# Jacks_EDCPSU.net
KiCad netlist of a schematic drawn in EAGLE
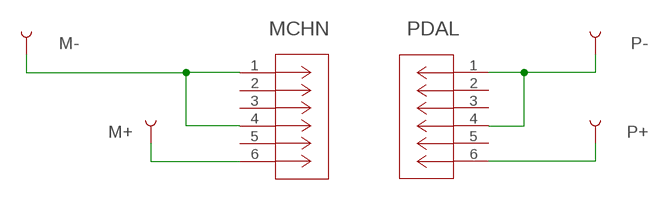
[diagram p0: schematic, sheet 1]

(export (version "E")
  (design (tool "Eeschema 10.0.6"))
  (components
    (comp (ref "M+")
      (value "TEST-POINT3")
      (footprint "eagle-import:PAD.03X.03")
      (libsource (lib "eagle-import") (part "TEST-POINT3"))
    )
    (comp (ref "M-")
      (value "TEST-POINT3")
      (footprint "eagle-import:PAD.03X.03")
      (libsource (lib "eagle-import") (part "TEST-POINT3"))
    )
    (comp (ref "MCHN")
      (value "ACJS-MHDR")
      (footprint "eagle-import:CONN_MHDR_AMP")
      (fields (field (name "COPYRIGHT") "Copyright (C) 2018 Accelerated Designs. All rights reserved"))
      (libsource (lib "eagle-import") (part "ACJS-MHDR"))
    )
    (comp (ref "P+")
      (value "TEST-POINT3")
      (footprint "eagle-import:PAD.03X.03")
      (libsource (lib "eagle-import") (part "TEST-POINT3"))
    )
    (comp (ref "P-")
      (value "TEST-POINT3")
      (footprint "eagle-import:PAD.03X.03")
      (libsource (lib "eagle-import") (part "TEST-POINT3"))
    )
    (comp (ref "PDAL")
      (value "ACJS-MHDR")
      (footprint "eagle-import:CONN_MHDR_AMP")
      (fields (field (name "COPYRIGHT") "Copyright (C) 2018 Accelerated Designs. All rights reserved"))
      (libsource (lib "eagle-import") (part "ACJS-MHDR"))
    )
  )
  (nets
    (net (code "1") (name "Net-(M+-1)") (class "Default")
      (node (ref "M+") (pin "P$1") (pinfunction "1_P$1") (pintype "bidirectional"))
      (node (ref "MCHN") (pin "6") (pinfunction "6_6") (pintype "passive"))
    )
    (net (code "2") (name "Net-(M--1)") (class "Default")
      (node (ref "M-") (pin "P$1") (pinfunction "1_P$1") (pintype "bidirectional"))
      (node (ref "MCHN") (pin "1") (pinfunction "1_1") (pintype "passive"))
      (node (ref "MCHN") (pin "4") (pinfunction "4_4") (pintype "passive"))
    )
    (net (code "3") (name "Net-(P+-1)") (class "Default")
      (node (ref "P+") (pin "P$1") (pinfunction "1_P$1") (pintype "bidirectional"))
      (node (ref "PDAL") (pin "6") (pinfunction "6_6") (pintype "passive"))
    )
    (net (code "4") (name "Net-(P--1)") (class "Default")
      (node (ref "P-") (pin "P$1") (pinfunction "1_P$1") (pintype "bidirectional"))
      (node (ref "PDAL") (pin "1") (pinfunction "1_1") (pintype "passive"))
      (node (ref "PDAL") (pin "4") (pinfunction "4_4") (pintype "passive"))
    )
    (net (code "5") (name "unconnected-(MCHN-Pad2)") (class "Default")
      (node (ref "MCHN") (pin "2") (pinfunction "2_2") (pintype "passive"))
    )
    (net (code "6") (name "unconnected-(MCHN-Pad3)") (class "Default")
      (node (ref "MCHN") (pin "3") (pinfunction "3_3") (pintype "passive"))
    )
    (net (code "7") (name "unconnected-(MCHN-Pad5)") (class "Default")
      (node (ref "MCHN") (pin "5") (pinfunction "5_5") (pintype "passive"))
    )
    (net (code "8") (name "unconnected-(PDAL-Pad2)") (class "Default")
      (node (ref "PDAL") (pin "2") (pinfunction "2_2") (pintype "passive"))
    )
    (net (code "9") (name "unconnected-(PDAL-Pad3)") (class "Default")
      (node (ref "PDAL") (pin "3") (pinfunction "3_3") (pintype "passive"))
    )
    (net (code "10") (name "unconnected-(PDAL-Pad5)") (class "Default")
      (node (ref "PDAL") (pin "5") (pinfunction "5_5") (pintype "passive"))
    )
  )
)
